# blue_plant_1_0.net
KiCad netlist of a schematic drawn in EAGLE
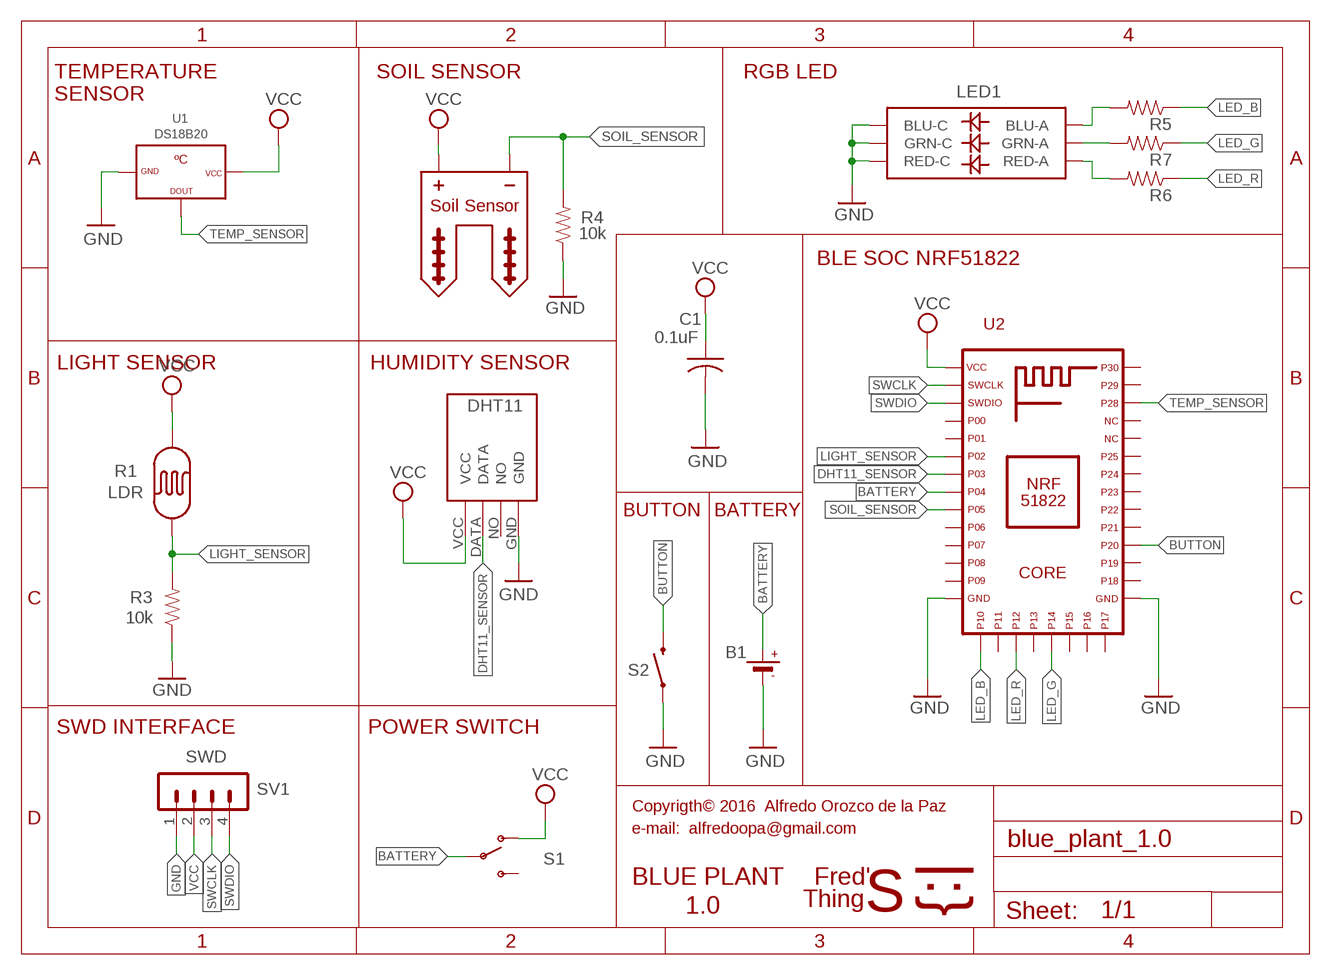
[diagram p0: schematic, sheet 1]

(export (version "E")
  (design (tool "Eeschema 10.0.6"))
  (components
    (comp (ref "B1")
      (value "BATTERYCR2032")
      (footprint "eagle-import:CR2032")
      (libsource (lib "eagle-import") (part "BATTERYCR2032"))
    )
    (comp (ref "C1")
      (value "0.1uF")
      (footprint "eagle-import:C025_050-025X075")
      (libsource (lib "eagle-import") (part "C-US025_050-025X075"))
    )
    (comp (ref "LED1")
      (value "RGB-5050")
      (footprint "eagle-import:LED-TRICOLOR-5050")
      (libsource (lib "eagle-import") (part "LED-TRICOLOR-5050NO_IC"))
    )
    (comp (ref "R1")
      (value "LDR")
      (footprint "eagle-import:PHOTOCELL-KIT")
      (libsource (lib "eagle-import") (part "PHOTOCELLPTH-KIT"))
    )
    (comp (ref "R2")
      (value "SOIL-SENSOR")
      (footprint "eagle-import:SOIL-SENSOR-1")
      (libsource (lib "eagle-import") (part "SOIL-SENSOR"))
    )
    (comp (ref "R3")
      (value "10k")
      (footprint "eagle-import:AXIAL-0.3-KIT")
      (libsource (lib "eagle-import") (part "RESISTORKIT"))
    )
    (comp (ref "R4")
      (value "10k")
      (footprint "eagle-import:AXIAL-0.3-KIT")
      (libsource (lib "eagle-import") (part "RESISTORKIT"))
    )
    (comp (ref "R5")
      (value "RESISTORKIT")
      (footprint "eagle-import:AXIAL-0.3-KIT")
      (libsource (lib "eagle-import") (part "RESISTORKIT"))
    )
    (comp (ref "R6")
      (value "RESISTORKIT")
      (footprint "eagle-import:AXIAL-0.3-KIT")
      (libsource (lib "eagle-import") (part "RESISTORKIT"))
    )
    (comp (ref "R7")
      (value "RESISTORKIT")
      (footprint "eagle-import:AXIAL-0.3-KIT")
      (libsource (lib "eagle-import") (part "RESISTORKIT"))
    )
    (comp (ref "S1")
      (value "SWITCH-SPDT-SMD-A")
      (footprint "eagle-import:SWITCH-SPST-SMD-A")
      (libsource (lib "eagle-import") (part "SWITCH-SPDT-SMD-A"))
    )
    (comp (ref "S2")
      (value "SWITCH-MOMENTARY-2SMD")
      (footprint "eagle-import:TACTILE_SWITCH_SMD")
      (libsource (lib "eagle-import") (part "SWITCH-MOMENTARY-2SMD"))
    )
    (comp (ref "SV1")
      (value "SWD")
      (footprint "eagle-import:MA04-1")
      (libsource (lib "eagle-import") (part "MA04-1"))
    )
    (comp (ref "U$1")
      (value "DHT11")
      (footprint "eagle-import:DHT11")
      (libsource (lib "eagle-import") (part "DHT11"))
    )
    (comp (ref "U1")
      (value "DS18B20")
      (footprint "eagle-import:TO-92")
      (libsource (lib "eagle-import") (part "DS18B20"))
    )
    (comp (ref "U2")
      (value "NRF51822-CORE-2")
      (footprint "eagle-import:NRF51822-CORE2")
      (libsource (lib "eagle-import") (part "NRF51822-CORE-2"))
    )
  )
  (nets
    (net (code "1") (name "BATTERY") (class "Default")
      (node (ref "B1") (pin "+") (pinfunction "+_+") (pintype "passive"))
      (node (ref "S1") (pin "2") (pinfunction "P_2") (pintype "passive"))
      (node (ref "U2") (pin "P18") (pinfunction "P04_P18") (pintype "bidirectional"))
    )
    (net (code "2") (name "BUTTON") (class "Default")
      (node (ref "S2") (pin "3") (pinfunction "2_3") (pintype "passive"))
      (node (ref "U2") (pin "P20") (pinfunction "P20_P20") (pintype "bidirectional"))
    )
    (net (code "3") (name "DHT11_SENSOR") (class "Default")
      (node (ref "U$1") (pin "DATA") (pinfunction "DATA_DATA") (pintype "bidirectional"))
      (node (ref "U2") (pin "P17") (pinfunction "P03_P17") (pintype "bidirectional"))
    )
    (net (code "4") (name "GND") (class "Default")
      (node (ref "B1") (pin "-") (pinfunction "-_-") (pintype "passive"))
      (node (ref "C1") (pin "2") (pinfunction "2_2") (pintype "passive"))
      (node (ref "LED1") (pin "4") (pinfunction "BLU-C_4") (pintype "bidirectional"))
      (node (ref "LED1") (pin "5") (pinfunction "RED-C_5") (pintype "bidirectional"))
      (node (ref "LED1") (pin "6") (pinfunction "GRN-C_6") (pintype "bidirectional"))
      (node (ref "R3") (pin "P$1") (pinfunction "1_P$1") (pintype "passive"))
      (node (ref "R4") (pin "P$1") (pinfunction "1_P$1") (pintype "passive"))
      (node (ref "S2") (pin "1") (pinfunction "1_1") (pintype "passive"))
      (node (ref "SV1") (pin "1") (pinfunction "1_1") (pintype "passive"))
      (node (ref "U$1") (pin "GND") (pinfunction "GND_GND") (pintype "bidirectional"))
      (node (ref "U1") (pin "1") (pinfunction "GND_1") (pintype "power_in"))
      (node (ref "U2") (pin "P1") (pinfunction "GND1_P1") (pintype "power_in"))
      (node (ref "U2") (pin "P12") (pinfunction "GND2_P12") (pintype "power_in"))
    )
    (net (code "5") (name "LED_B") (class "Default")
      (node (ref "R5") (pin "P$1") (pinfunction "1_P$1") (pintype "passive"))
      (node (ref "U2") (pin "P32") (pinfunction "P10_P32") (pintype "bidirectional"))
    )
    (net (code "6") (name "LED_G") (class "Default")
      (node (ref "R7") (pin "P$1") (pinfunction "1_P$1") (pintype "passive"))
      (node (ref "U2") (pin "P28") (pinfunction "P14_P28") (pintype "bidirectional"))
    )
    (net (code "7") (name "LED_R") (class "Default")
      (node (ref "R6") (pin "P$1") (pinfunction "1_P$1") (pintype "passive"))
      (node (ref "U2") (pin "P30") (pinfunction "P12_P30") (pintype "bidirectional"))
    )
    (net (code "8") (name "LIGHT_SENSOR") (class "Default")
      (node (ref "R1") (pin "1") (pinfunction "P$1_1") (pintype "bidirectional"))
      (node (ref "R3") (pin "P$2") (pinfunction "2_P$2") (pintype "passive"))
      (node (ref "U2") (pin "P16") (pinfunction "P02_P16") (pintype "bidirectional"))
    )
    (net (code "9") (name "Net-(LED1-BLU-A)") (class "Default")
      (node (ref "LED1") (pin "3") (pinfunction "BLU-A_3") (pintype "bidirectional"))
      (node (ref "R5") (pin "P$2") (pinfunction "2_P$2") (pintype "passive"))
    )
    (net (code "10") (name "Net-(LED1-GRN-A)") (class "Default")
      (node (ref "LED1") (pin "1") (pinfunction "GRN-A_1") (pintype "bidirectional"))
      (node (ref "R7") (pin "P$2") (pinfunction "2_P$2") (pintype "passive"))
    )
    (net (code "11") (name "Net-(LED1-RED-A)") (class "Default")
      (node (ref "LED1") (pin "2") (pinfunction "RED-A_2") (pintype "bidirectional"))
      (node (ref "R6") (pin "P$2") (pinfunction "2_P$2") (pintype "passive"))
    )
    (net (code "12") (name "SOIL_SENSOR") (class "Default")
      (node (ref "R2") (pin "P$1") (pinfunction "PG_P$1") (pintype "bidirectional"))
      (node (ref "R4") (pin "P$2") (pinfunction "2_P$2") (pintype "passive"))
      (node (ref "U2") (pin "P35") (pinfunction "P05_P35") (pintype "bidirectional"))
    )
    (net (code "13") (name "SWCLK") (class "Default")
      (node (ref "SV1") (pin "3") (pinfunction "3_3") (pintype "passive"))
      (node (ref "U2") (pin "P24") (pinfunction "SWDCLK_P24") (pintype "bidirectional"))
    )
    (net (code "14") (name "SWDIO") (class "Default")
      (node (ref "SV1") (pin "4") (pinfunction "4_4") (pintype "passive"))
      (node (ref "U2") (pin "P23") (pinfunction "SWDIO_P23") (pintype "bidirectional"))
    )
    (net (code "15") (name "TEMP_SENSOR") (class "Default")
      (node (ref "U1") (pin "2") (pinfunction "DOUT_2") (pintype "output"))
      (node (ref "U2") (pin "P9") (pinfunction "P28_P9") (pintype "bidirectional"))
    )
    (net (code "16") (name "VCC") (class "Default")
      (node (ref "C1") (pin "1") (pinfunction "1_1") (pintype "passive"))
      (node (ref "R1") (pin "2") (pinfunction "P$2_2") (pintype "bidirectional"))
      (node (ref "R2") (pin "P$2") (pinfunction "PS_P$2") (pintype "bidirectional"))
      (node (ref "S1") (pin "1") (pinfunction "O_1") (pintype "passive"))
      (node (ref "SV1") (pin "2") (pinfunction "2_2") (pintype "passive"))
      (node (ref "U$1") (pin "VCC") (pinfunction "VCC_VCC") (pintype "bidirectional"))
      (node (ref "U1") (pin "3") (pinfunction "VCC_3") (pintype "power_in"))
      (node (ref "U2") (pin "P11") (pinfunction "VCC_P11") (pintype "power_in"))
    )
    (net (code "17") (name "unconnected-(S1-S-Pad3)") (class "Default")
      (node (ref "S1") (pin "3") (pinfunction "S_3") (pintype "passive"))
    )
    (net (code "18") (name "unconnected-(U$1-PadNO)") (class "Default")
      (node (ref "U$1") (pin "NO") (pinfunction "NO_NO") (pintype "bidirectional"))
    )
    (net (code "19") (name "unconnected-(U2-P00-PadP14)") (class "Default")
      (node (ref "U2") (pin "P14") (pinfunction "P00_P14") (pintype "bidirectional"))
    )
    (net (code "20") (name "unconnected-(U2-P01-PadP15)") (class "Default")
      (node (ref "U2") (pin "P15") (pinfunction "P01_P15") (pintype "bidirectional"))
    )
    (net (code "21") (name "unconnected-(U2-P06-PadP36)") (class "Default")
      (node (ref "U2") (pin "P36") (pinfunction "P06_P36") (pintype "bidirectional"))
    )
    (net (code "22") (name "unconnected-(U2-P07-PadP33)") (class "Default")
      (node (ref "U2") (pin "P33") (pinfunction "P07_P33") (pintype "bidirectional"))
    )
    (net (code "23") (name "unconnected-(U2-P08-PadP34)") (class "Default")
      (node (ref "U2") (pin "P34") (pinfunction "P08_P34") (pintype "bidirectional"))
    )
    (net (code "24") (name "unconnected-(U2-P09-PadP31)") (class "Default")
      (node (ref "U2") (pin "P31") (pinfunction "P09_P31") (pintype "bidirectional"))
    )
    (net (code "25") (name "unconnected-(U2-P11-PadP29)") (class "Default")
      (node (ref "U2") (pin "P29") (pinfunction "P11_P29") (pintype "bidirectional"))
    )
    (net (code "26") (name "unconnected-(U2-P13-PadP27)") (class "Default")
      (node (ref "U2") (pin "P27") (pinfunction "P13_P27") (pintype "bidirectional"))
    )
    (net (code "27") (name "unconnected-(U2-P15-PadP25)") (class "Default")
      (node (ref "U2") (pin "P25") (pinfunction "P15_P25") (pintype "bidirectional"))
    )
    (net (code "28") (name "unconnected-(U2-P16-PadP26)") (class "Default")
      (node (ref "U2") (pin "P26") (pinfunction "P16_P26") (pintype "bidirectional"))
    )
    (net (code "29") (name "unconnected-(U2-P17-PadP21)") (class "Default")
      (node (ref "U2") (pin "P21") (pinfunction "P17_P21") (pintype "bidirectional"))
    )
    (net (code "30") (name "unconnected-(U2-P18-PadP19)") (class "Default")
      (node (ref "U2") (pin "P19") (pinfunction "P18_P19") (pintype "bidirectional"))
    )
    (net (code "31") (name "unconnected-(U2-P19-PadP22)") (class "Default")
      (node (ref "U2") (pin "P22") (pinfunction "P19_P22") (pintype "bidirectional"))
    )
    (net (code "32") (name "unconnected-(U2-P21-PadP2)") (class "Default")
      (node (ref "U2") (pin "P2") (pinfunction "P21_P2") (pintype "bidirectional"))
    )
    (net (code "33") (name "unconnected-(U2-P22-PadP3)") (class "Default")
      (node (ref "U2") (pin "P3") (pinfunction "P22_P3") (pintype "bidirectional"))
    )
    (net (code "34") (name "unconnected-(U2-P23-PadP4)") (class "Default")
      (node (ref "U2") (pin "P4") (pinfunction "P23_P4") (pintype "bidirectional"))
    )
    (net (code "35") (name "unconnected-(U2-P24-PadP5)") (class "Default")
      (node (ref "U2") (pin "P5") (pinfunction "P24_P5") (pintype "bidirectional"))
    )
    (net (code "36") (name "unconnected-(U2-P25-PadP6)") (class "Default")
      (node (ref "U2") (pin "P6") (pinfunction "P25_P6") (pintype "bidirectional"))
    )
    (net (code "37") (name "unconnected-(U2-P26-PadP7)") (class "Default")
      (node (ref "U2") (pin "P7") (pinfunction "P26_P7") (pintype "no_connect"))
    )
    (net (code "38") (name "unconnected-(U2-P27-PadP8)") (class "Default")
      (node (ref "U2") (pin "P8") (pinfunction "P27_P8") (pintype "no_connect"))
    )
    (net (code "39") (name "unconnected-(U2-P29-PadP10)") (class "Default")
      (node (ref "U2") (pin "P10") (pinfunction "P29_P10") (pintype "bidirectional"))
    )
    (net (code "40") (name "unconnected-(U2-P30-PadP13)") (class "Default")
      (node (ref "U2") (pin "P13") (pinfunction "P30_P13") (pintype "bidirectional"))
    )
  )
)
